# sch_qtouch.net
KiCad netlist of a schematic drawn in Altium Designer
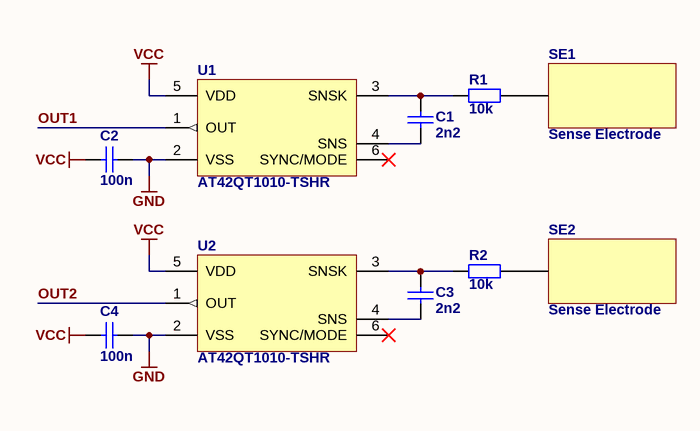
[diagram p0: sch_qtouch.SchDoc]

(export (version "E")
  (design (tool "Eeschema 10.0.6"))
  (components
    (comp (ref "C1")
      (value "2n2")
      (footprint "C0603")
      (description "Capacitor")
      (libsource (lib "capacitors") (part "Cap"))
    )
    (comp (ref "C2")
      (value "100n")
      (footprint "C0603")
      (description "Capacitor")
      (libsource (lib "capacitors") (part "Cap"))
    )
    (comp (ref "C3")
      (value "2n2")
      (footprint "C0603")
      (description "Capacitor")
      (libsource (lib "capacitors") (part "Cap"))
    )
    (comp (ref "C4")
      (value "100n")
      (footprint "C0603")
      (description "Capacitor")
      (libsource (lib "capacitors") (part "Cap"))
    )
    (comp (ref "R1")
      (value "10k")
      (footprint "R0603")
      (description "Resistor")
      (libsource (lib "resistors") (part "Res"))
    )
    (comp (ref "R2")
      (value "10k")
      (footprint "R0603")
      (description "Resistor")
      (libsource (lib "resistors") (part "Res"))
    )
    (comp (ref "SE1")
      (value "Sense Electrode")
      (footprint "SNS_EL_CIRC_1cm")
      (description "Circular (1cm Diameter) Sense Electrode")
      (libsource (lib "capactitive_interface_sensors_and_ics") (part "_SNS_EL_CIRC_1cm"))
    )
    (comp (ref "SE2")
      (value "Sense Electrode")
      (footprint "SNS_EL_CIRC_1cm")
      (description "Circular (1cm Diameter) Sense Electrode")
      (libsource (lib "capactitive_interface_sensors_and_ics") (part "_SNS_EL_CIRC_1cm"))
    )
    (comp (ref "U1")
      (value "AT42QT1010-TSHR")
      (footprint "SOT-23-6")
      (description "Atmel Single-key QTouch Touch Sensor IC")
      (libsource (lib "capacitive_interface_sensors_and_ics") (part "AT42QT1010-TSHR"))
    )
    (comp (ref "U2")
      (value "AT42QT1010-TSHR")
      (footprint "SOT-23-6")
      (description "Atmel Single-key QTouch Touch Sensor IC")
      (libsource (lib "capacitive_interface_sensors_and_ics") (part "AT42QT1010-TSHR"))
    )
  )
  (nets
    (net (code "1") (name "/OUT1") (class "Default")
      (node (ref "U1") (pin "1") (pinfunction "OUT_1") (pintype "output"))
    )
    (net (code "2") (name "/OUT2") (class "Default")
      (node (ref "U2") (pin "1") (pinfunction "OUT_1") (pintype "output"))
    )
    (net (code "3") (name "GND") (class "Default")
      (node (ref "C2") (pin "1") (pinfunction "1_1") (pintype "passive"))
      (node (ref "C4") (pin "1") (pinfunction "1_1") (pintype "passive"))
      (node (ref "U1") (pin "2") (pinfunction "VSS_2") (pintype "passive"))
      (node (ref "U2") (pin "2") (pinfunction "VSS_2") (pintype "passive"))
    )
    (net (code "4") (name "Net-(SE1-SE)") (class "Default")
      (node (ref "R1") (pin "2") (pinfunction "2_2") (pintype "passive"))
      (node (ref "SE1") (pin "1") (pinfunction "SE_1") (pintype "passive"))
    )
    (net (code "5") (name "Net-(SE2-SE)") (class "Default")
      (node (ref "R2") (pin "2") (pinfunction "2_2") (pintype "passive"))
      (node (ref "SE2") (pin "1") (pinfunction "SE_1") (pintype "passive"))
    )
    (net (code "6") (name "Net-(U1-SNS)") (class "Default")
      (node (ref "C1") (pin "1") (pinfunction "1_1") (pintype "passive"))
      (node (ref "U1") (pin "4") (pinfunction "SNS_4") (pintype "passive"))
    )
    (net (code "7") (name "Net-(U1-SNSK)") (class "Default")
      (node (ref "C1") (pin "2") (pinfunction "2_2") (pintype "passive"))
      (node (ref "R1") (pin "1") (pinfunction "1_1") (pintype "passive"))
      (node (ref "U1") (pin "3") (pinfunction "SNSK_3") (pintype "passive"))
    )
    (net (code "8") (name "Net-(U2-SNS)") (class "Default")
      (node (ref "C3") (pin "1") (pinfunction "1_1") (pintype "passive"))
      (node (ref "U2") (pin "4") (pinfunction "SNS_4") (pintype "passive"))
    )
    (net (code "9") (name "Net-(U2-SNSK)") (class "Default")
      (node (ref "C3") (pin "2") (pinfunction "2_2") (pintype "passive"))
      (node (ref "R2") (pin "1") (pinfunction "1_1") (pintype "passive"))
      (node (ref "U2") (pin "3") (pinfunction "SNSK_3") (pintype "passive"))
    )
    (net (code "10") (name "VCC") (class "Default")
      (node (ref "C2") (pin "2") (pinfunction "2_2") (pintype "passive"))
      (node (ref "C4") (pin "2") (pinfunction "2_2") (pintype "passive"))
      (node (ref "U1") (pin "5") (pinfunction "VDD_5") (pintype "passive"))
      (node (ref "U2") (pin "5") (pinfunction "VDD_5") (pintype "passive"))
    )
    (net (code "11") (name "unconnected-(U1-SYNC{slash}MODE-Pad6)") (class "Default")
      (node (ref "U1") (pin "6") (pinfunction "SYNC/MODE_6") (pintype "passive+no_connect"))
    )
    (net (code "12") (name "unconnected-(U2-SYNC{slash}MODE-Pad6)") (class "Default")
      (node (ref "U2") (pin "6") (pinfunction "SYNC/MODE_6") (pintype "passive+no_connect"))
    )
  )
)
